# dual-ecal-RF-board.net
KiCad netlist of a schematic drawn in Altium Designer
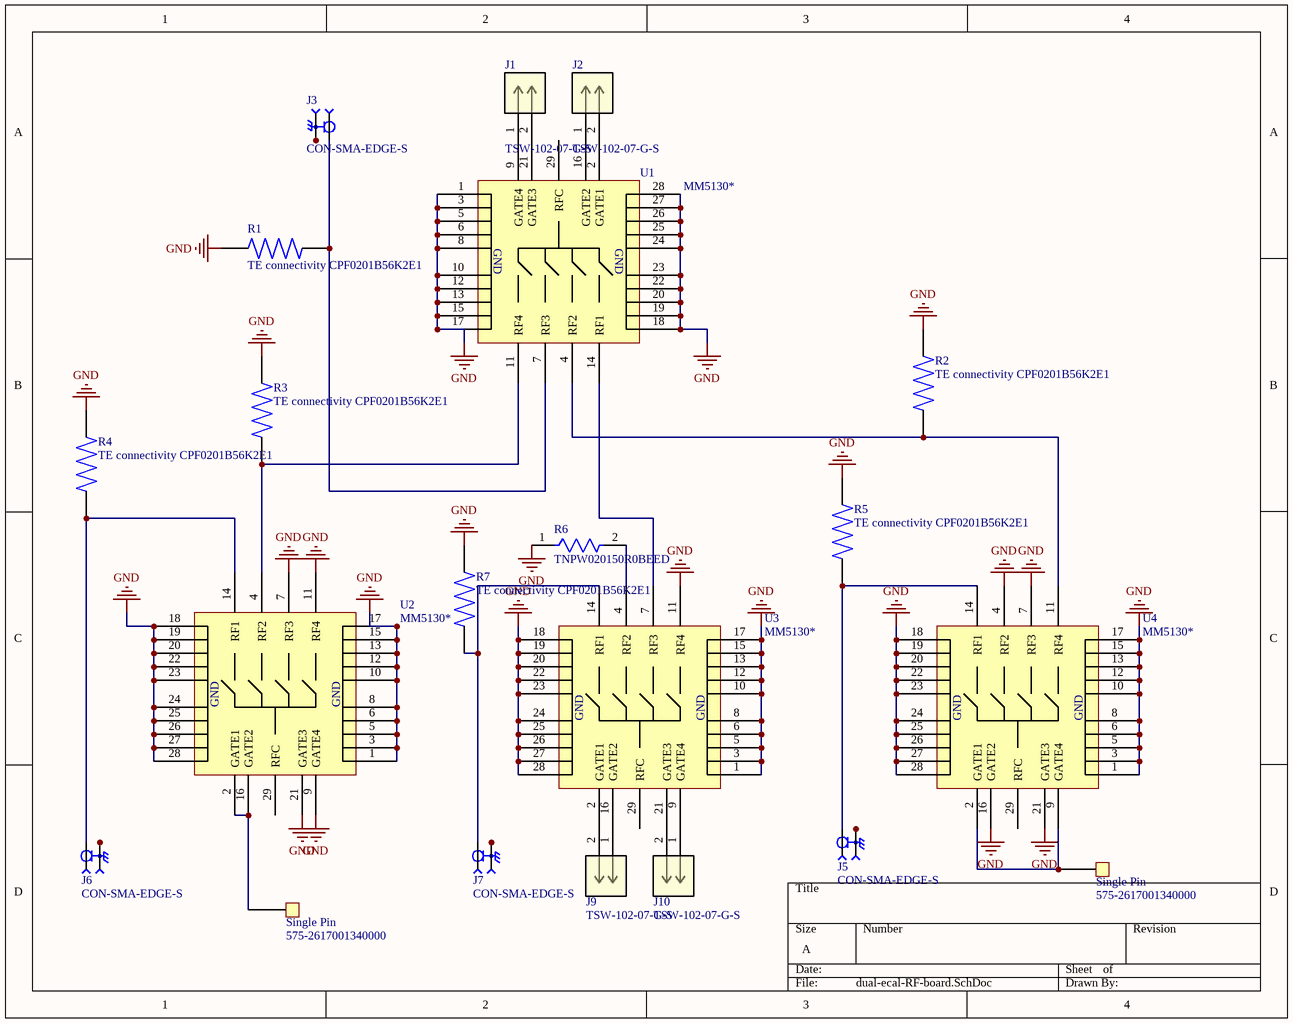
[diagram p0: dual-ecal-RF-board.SchDoc]

(export (version "E")
  (design (tool "Eeschema 10.0.6"))
  (components
    (comp (ref "J1")
      (value "TSW-102-07-G-S")
      (footprint "TSW-102-07-G-S-iceberg")
      (description "No Description Available")
      (fields (field (name "COPYRIGHT") "Copyright (C) 2024 Ultra Librarian. All rights reserved."))
      (libsource (lib "SchlibLafe") (part "TSW-102-07-G-S-iceberg"))
    )
    (comp (ref "J2")
      (value "TSW-102-07-G-S")
      (footprint "TSW-102-07-G-S-iceberg")
      (description "No Description Available")
      (fields (field (name "COPYRIGHT") "Copyright (C) 2024 Ultra Librarian. All rights reserved."))
      (libsource (lib "SchlibLafe") (part "TSW-102-07-G-S-iceberg"))
    )
    (comp (ref "J3")
      (value "CON-SMA-EDGE-S")
      (footprint "RFSOLUTIONS_CON-SMA-EDGE-S")
      (description "SMA Connector Jack, Female Socket - Board Edge, End Launch Solder")
      (fields (field (name "MF") "RF Solutions") (field (name "DIGI-KEY_PART_NUMBER") "CON-SMA-EDGE-S-ND"))
      (libsource (lib "SchlibLafe") (part "CON-SMA-EDGE-S"))
    )
    (comp (ref "J4")
      (value "Single Pin")
      (footprint "Single PC Pin")
      (fields (field (name "SUPPLIER PART NUMBER 1") "575-2617001340000"))
      (libsource (lib "SchlibLafe") (part "Single PC Pin"))
    )
    (comp (ref "J5")
      (value "CON-SMA-EDGE-S")
      (footprint "RFSOLUTIONS_CON-SMA-EDGE-S")
      (description "SMA Connector Jack, Female Socket - Board Edge, End Launch Solder")
      (fields (field (name "MF") "RF Solutions") (field (name "DIGI-KEY_PART_NUMBER") "CON-SMA-EDGE-S-ND"))
      (libsource (lib "SchlibLafe") (part "CON-SMA-EDGE-S"))
    )
    (comp (ref "J6")
      (value "CON-SMA-EDGE-S")
      (footprint "RFSOLUTIONS_CON-SMA-EDGE-S")
      (description "SMA Connector Jack, Female Socket - Board Edge, End Launch Solder")
      (fields (field (name "MF") "RF Solutions") (field (name "DIGI-KEY_PART_NUMBER") "CON-SMA-EDGE-S-ND"))
      (libsource (lib "SchlibLafe") (part "CON-SMA-EDGE-S"))
    )
    (comp (ref "J7")
      (value "CON-SMA-EDGE-S")
      (footprint "RFSOLUTIONS_CON-SMA-EDGE-S")
      (description "SMA Connector Jack, Female Socket - Board Edge, End Launch Solder")
      (fields (field (name "MF") "RF Solutions") (field (name "DIGI-KEY_PART_NUMBER") "CON-SMA-EDGE-S-ND"))
      (libsource (lib "SchlibLafe") (part "CON-SMA-EDGE-S"))
    )
    (comp (ref "J8")
      (value "Single Pin")
      (footprint "Single PC Pin")
      (fields (field (name "SUPPLIER PART NUMBER 1") "575-2617001340000"))
      (libsource (lib "SchlibLafe") (part "Single PC Pin"))
    )
    (comp (ref "J9")
      (value "TSW-102-07-G-S")
      (footprint "TSW-102-07-G-S-iceberg")
      (description "No Description Available")
      (fields (field (name "COPYRIGHT") "Copyright (C) 2024 Ultra Librarian. All rights reserved."))
      (libsource (lib "") (part "TSW-102-07-G-S-iceberg_1"))
    )
    (comp (ref "J10")
      (value "TSW-102-07-G-S")
      (footprint "TSW-102-07-G-S-iceberg")
      (description "No Description Available")
      (fields (field (name "COPYRIGHT") "Copyright (C) 2024 Ultra Librarian. All rights reserved."))
      (libsource (lib "") (part "TSW-102-07-G-S-iceberg_1"))
    )
    (comp (ref "R1")
      (value "TE connectivity CPF0201B56K2E1")
      (footprint "0201-resistor")
      (description "CPF 0201 56K2 0.1% 25PPM 1K RL")
      (fields (field (name "MP") "ERJ1GN0R00C") (field (name "MFGR PART NO.") "CPF0201B56K2E1"))
      (libsource (lib "SchlibLafe") (part "TE connectivity CPF0201B56K2E1"))
    )
    (comp (ref "R2")
      (value "TE connectivity CPF0201B56K2E1")
      (footprint "0201-resistor")
      (description "CPF 0201 56K2 0.1% 25PPM 1K RL")
      (fields (field (name "MP") "ERJ1GN0R00C") (field (name "MFGR PART NO.") "CPF0201B56K2E1"))
      (libsource (lib "SchlibLafe") (part "TE connectivity CPF0201B56K2E1"))
    )
    (comp (ref "R3")
      (value "TE connectivity CPF0201B56K2E1")
      (footprint "0201-resistor")
      (description "CPF 0201 56K2 0.1% 25PPM 1K RL")
      (fields (field (name "MP") "ERJ1GN0R00C") (field (name "MFGR PART NO.") "CPF0201B56K2E1"))
      (libsource (lib "SchlibLafe") (part "TE connectivity CPF0201B56K2E1"))
    )
    (comp (ref "R4")
      (value "TE connectivity CPF0201B56K2E1")
      (footprint "0201-resistor")
      (description "CPF 0201 56K2 0.1% 25PPM 1K RL")
      (fields (field (name "MP") "ERJ1GN0R00C") (field (name "MFGR PART NO.") "CPF0201B56K2E1"))
      (libsource (lib "SchlibLafe") (part "TE connectivity CPF0201B56K2E1"))
    )
    (comp (ref "R5")
      (value "TE connectivity CPF0201B56K2E1")
      (footprint "0201-resistor")
      (description "CPF 0201 56K2 0.1% 25PPM 1K RL")
      (fields (field (name "MP") "ERJ1GN0R00C") (field (name "MFGR PART NO.") "CPF0201B56K2E1"))
      (libsource (lib "SchlibLafe") (part "TE connectivity CPF0201B56K2E1"))
    )
    (comp (ref "R6")
      (value "TNPW020150R0BEED")
      (footprint "FP-ERJ1GN-IPC_C")
      (description "RES SMD 50 OHM 0.1% 1/20W 0201")
      (fields (field (name "TOLERANCE") "1%"))
      (libsource (lib "Altium Content Vault") (part "1029c3af85768c4190bb7ad29bc67b5"))
    )
    (comp (ref "R7")
      (value "TE connectivity CPF0201B56K2E1")
      (footprint "0201-resistor")
      (description "CPF 0201 56K2 0.1% 25PPM 1K RL")
      (fields (field (name "MP") "ERJ1GN0R00C") (field (name "MFGR PART NO.") "CPF0201B56K2E1"))
      (libsource (lib "SchlibLafe") (part "TE connectivity CPF0201B56K2E1"))
    )
    (comp (ref "U1")
      (value "MM5130*")
      (footprint "MM5130-NORM_PCB_NOFLOOD")
      (description "High power SP4T MEMs switch")
      (libsource (lib "") (part "IC-MM5130_1"))
    )
    (comp (ref "U2")
      (value "MM5130*")
      (footprint "MM5130-NORM_PCB_NOFLOOD")
      (description "High power SP4T MEMs switch")
      (libsource (lib "MM5130_SCHSYM") (part "IC-MM5130"))
    )
    (comp (ref "U3")
      (value "MM5130*")
      (footprint "MM5130-NORM_PCB_NOFLOOD")
      (description "High power SP4T MEMs switch")
      (libsource (lib "MM5130_SCHSYM") (part "IC-MM5130"))
    )
    (comp (ref "U4")
      (value "MM5130*")
      (footprint "MM5130-NORM_PCB_NOFLOOD")
      (description "High power SP4T MEMs switch")
      (libsource (lib "MM5130_SCHSYM") (part "IC-MM5130"))
    )
  )
  (nets
    (net (code "1") (name "GND") (class "Default")
      (node (ref "R1") (pin "1") (pinfunction "1_1") (pintype "passive"))
      (node (ref "R2") (pin "1") (pinfunction "1_1") (pintype "passive"))
      (node (ref "R3") (pin "1") (pinfunction "1_1") (pintype "passive"))
      (node (ref "R4") (pin "1") (pinfunction "1_1") (pintype "passive"))
      (node (ref "R5") (pin "1") (pinfunction "1_1") (pintype "passive"))
      (node (ref "R6") (pin "1") (pinfunction "1_1") (pintype "passive"))
      (node (ref "R7") (pin "1") (pinfunction "1_1") (pintype "passive"))
      (node (ref "U1") (pin "1") (pinfunction "GND_1") (pintype "passive"))
      (node (ref "U1") (pin "10") (pinfunction "GND_10") (pintype "passive"))
      (node (ref "U1") (pin "12") (pinfunction "GND_12") (pintype "passive"))
      (node (ref "U1") (pin "13") (pinfunction "GND_13") (pintype "passive"))
      (node (ref "U1") (pin "15") (pinfunction "GND_15") (pintype "passive"))
      (node (ref "U1") (pin "17") (pinfunction "GND_17") (pintype "passive"))
      (node (ref "U1") (pin "18") (pinfunction "GND_18") (pintype "passive"))
      (node (ref "U1") (pin "19") (pinfunction "GND_19") (pintype "passive"))
      (node (ref "U1") (pin "20") (pinfunction "GND_20") (pintype "passive"))
      (node (ref "U1") (pin "22") (pinfunction "GND_22") (pintype "passive"))
      (node (ref "U1") (pin "23") (pinfunction "GND_23") (pintype "passive"))
      (node (ref "U1") (pin "24") (pinfunction "GND_24") (pintype "passive"))
      (node (ref "U1") (pin "25") (pinfunction "GND_25") (pintype "passive"))
      (node (ref "U1") (pin "26") (pinfunction "GND_26") (pintype "passive"))
      (node (ref "U1") (pin "27") (pinfunction "GND_27") (pintype "passive"))
      (node (ref "U1") (pin "28") (pinfunction "GND_28") (pintype "passive"))
      (node (ref "U1") (pin "3") (pinfunction "GND_3") (pintype "passive"))
      (node (ref "U1") (pin "5") (pinfunction "GND_5") (pintype "passive"))
      (node (ref "U1") (pin "6") (pinfunction "GND_6") (pintype "passive"))
      (node (ref "U1") (pin "8") (pinfunction "GND_8") (pintype "passive"))
      (node (ref "U2") (pin "1") (pinfunction "GND_1") (pintype "passive"))
      (node (ref "U2") (pin "10") (pinfunction "GND_10") (pintype "passive"))
      (node (ref "U2") (pin "11") (pinfunction "RF4_11") (pintype "passive"))
      (node (ref "U2") (pin "12") (pinfunction "GND_12") (pintype "passive"))
      (node (ref "U2") (pin "13") (pinfunction "GND_13") (pintype "passive"))
      (node (ref "U2") (pin "15") (pinfunction "GND_15") (pintype "passive"))
      (node (ref "U2") (pin "17") (pinfunction "GND_17") (pintype "passive"))
      (node (ref "U2") (pin "18") (pinfunction "GND_18") (pintype "passive"))
      (node (ref "U2") (pin "19") (pinfunction "GND_19") (pintype "passive"))
      (node (ref "U2") (pin "20") (pinfunction "GND_20") (pintype "passive"))
      (node (ref "U2") (pin "21") (pinfunction "GATE3_21") (pintype "passive"))
      (node (ref "U2") (pin "22") (pinfunction "GND_22") (pintype "passive"))
      (node (ref "U2") (pin "23") (pinfunction "GND_23") (pintype "passive"))
      (node (ref "U2") (pin "24") (pinfunction "GND_24") (pintype "passive"))
      (node (ref "U2") (pin "25") (pinfunction "GND_25") (pintype "passive"))
      (node (ref "U2") (pin "26") (pinfunction "GND_26") (pintype "passive"))
      (node (ref "U2") (pin "27") (pinfunction "GND_27") (pintype "passive"))
      (node (ref "U2") (pin "28") (pinfunction "GND_28") (pintype "passive"))
      (node (ref "U2") (pin "3") (pinfunction "GND_3") (pintype "passive"))
      (node (ref "U2") (pin "5") (pinfunction "GND_5") (pintype "passive"))
      (node (ref "U2") (pin "6") (pinfunction "GND_6") (pintype "passive"))
      (node (ref "U2") (pin "7") (pinfunction "RF3_7") (pintype "passive"))
      (node (ref "U2") (pin "8") (pinfunction "GND_8") (pintype "passive"))
      (node (ref "U2") (pin "9") (pinfunction "GATE4_9") (pintype "passive"))
      (node (ref "U3") (pin "1") (pinfunction "GND_1") (pintype "passive"))
      (node (ref "U3") (pin "10") (pinfunction "GND_10") (pintype "passive"))
      (node (ref "U3") (pin "11") (pinfunction "RF4_11") (pintype "passive"))
      (node (ref "U3") (pin "12") (pinfunction "GND_12") (pintype "passive"))
      (node (ref "U3") (pin "13") (pinfunction "GND_13") (pintype "passive"))
      (node (ref "U3") (pin "15") (pinfunction "GND_15") (pintype "passive"))
      (node (ref "U3") (pin "17") (pinfunction "GND_17") (pintype "passive"))
      (node (ref "U3") (pin "18") (pinfunction "GND_18") (pintype "passive"))
      (node (ref "U3") (pin "19") (pinfunction "GND_19") (pintype "passive"))
      (node (ref "U3") (pin "20") (pinfunction "GND_20") (pintype "passive"))
      (node (ref "U3") (pin "22") (pinfunction "GND_22") (pintype "passive"))
      (node (ref "U3") (pin "23") (pinfunction "GND_23") (pintype "passive"))
      (node (ref "U3") (pin "24") (pinfunction "GND_24") (pintype "passive"))
      (node (ref "U3") (pin "25") (pinfunction "GND_25") (pintype "passive"))
      (node (ref "U3") (pin "26") (pinfunction "GND_26") (pintype "passive"))
      (node (ref "U3") (pin "27") (pinfunction "GND_27") (pintype "passive"))
      (node (ref "U3") (pin "28") (pinfunction "GND_28") (pintype "passive"))
      (node (ref "U3") (pin "3") (pinfunction "GND_3") (pintype "passive"))
      (node (ref "U3") (pin "5") (pinfunction "GND_5") (pintype "passive"))
      (node (ref "U3") (pin "6") (pinfunction "GND_6") (pintype "passive"))
      (node (ref "U3") (pin "8") (pinfunction "GND_8") (pintype "passive"))
      (node (ref "U4") (pin "1") (pinfunction "GND_1") (pintype "passive"))
      (node (ref "U4") (pin "10") (pinfunction "GND_10") (pintype "passive"))
      (node (ref "U4") (pin "12") (pinfunction "GND_12") (pintype "passive"))
      (node (ref "U4") (pin "13") (pinfunction "GND_13") (pintype "passive"))
      (node (ref "U4") (pin "15") (pinfunction "GND_15") (pintype "passive"))
      (node (ref "U4") (pin "16") (pinfunction "GATE2_16") (pintype "passive"))
      (node (ref "U4") (pin "17") (pinfunction "GND_17") (pintype "passive"))
      (node (ref "U4") (pin "18") (pinfunction "GND_18") (pintype "passive"))
      (node (ref "U4") (pin "19") (pinfunction "GND_19") (pintype "passive"))
      (node (ref "U4") (pin "20") (pinfunction "GND_20") (pintype "passive"))
      (node (ref "U4") (pin "21") (pinfunction "GATE3_21") (pintype "passive"))
      (node (ref "U4") (pin "22") (pinfunction "GND_22") (pintype "passive"))
      (node (ref "U4") (pin "23") (pinfunction "GND_23") (pintype "passive"))
      (node (ref "U4") (pin "24") (pinfunction "GND_24") (pintype "passive"))
      (node (ref "U4") (pin "25") (pinfunction "GND_25") (pintype "passive"))
      (node (ref "U4") (pin "26") (pinfunction "GND_26") (pintype "passive"))
      (node (ref "U4") (pin "27") (pinfunction "GND_27") (pintype "passive"))
      (node (ref "U4") (pin "28") (pinfunction "GND_28") (pintype "passive"))
      (node (ref "U4") (pin "3") (pinfunction "GND_3") (pintype "passive"))
      (node (ref "U4") (pin "4") (pinfunction "RF2_4") (pintype "passive"))
      (node (ref "U4") (pin "5") (pinfunction "GND_5") (pintype "passive"))
      (node (ref "U4") (pin "6") (pinfunction "GND_6") (pintype "passive"))
      (node (ref "U4") (pin "7") (pinfunction "RF3_7") (pintype "passive"))
      (node (ref "U4") (pin "8") (pinfunction "GND_8") (pintype "passive"))
    )
    (net (code "2") (name "Net-(J3-2-PadG1)") (class "Default")
      (node (ref "J3") (pin "G1") (pinfunction "2_G1") (pintype "passive"))
      (node (ref "J3") (pin "G2") (pinfunction "2_G2") (pintype "passive"))
      (node (ref "J3") (pin "G3") (pinfunction "2_G3") (pintype "passive"))
      (node (ref "J3") (pin "G4") (pinfunction "2_G4") (pintype "passive"))
    )
    (net (code "3") (name "Net-(J5-2-PadG1)") (class "Default")
      (node (ref "J5") (pin "G1") (pinfunction "2_G1") (pintype "passive"))
      (node (ref "J5") (pin "G2") (pinfunction "2_G2") (pintype "passive"))
      (node (ref "J5") (pin "G3") (pinfunction "2_G3") (pintype "passive"))
      (node (ref "J5") (pin "G4") (pinfunction "2_G4") (pintype "passive"))
    )
    (net (code "4") (name "Net-(J6-2-PadG1)") (class "Default")
      (node (ref "J6") (pin "G1") (pinfunction "2_G1") (pintype "passive"))
      (node (ref "J6") (pin "G2") (pinfunction "2_G2") (pintype "passive"))
      (node (ref "J6") (pin "G3") (pinfunction "2_G3") (pintype "passive"))
      (node (ref "J6") (pin "G4") (pinfunction "2_G4") (pintype "passive"))
    )
    (net (code "5") (name "Net-(J7-2-PadG1)") (class "Default")
      (node (ref "J7") (pin "G1") (pinfunction "2_G1") (pintype "passive"))
      (node (ref "J7") (pin "G2") (pinfunction "2_G2") (pintype "passive"))
      (node (ref "J7") (pin "G3") (pinfunction "2_G3") (pintype "passive"))
      (node (ref "J7") (pin "G4") (pinfunction "2_G4") (pintype "passive"))
    )
    (net (code "6") (name "Net-(U1-GATE1)") (class "Default")
      (node (ref "J2") (pin "2") (pinfunction "2_2") (pintype "passive"))
      (node (ref "U1") (pin "2") (pinfunction "GATE1_2") (pintype "passive"))
    )
    (net (code "7") (name "Net-(U1-GATE2)") (class "Default")
      (node (ref "J2") (pin "1") (pinfunction "1_1") (pintype "passive"))
      (node (ref "U1") (pin "16") (pinfunction "GATE2_16") (pintype "passive"))
    )
    (net (code "8") (name "Net-(U1-GATE3)") (class "Default")
      (node (ref "J1") (pin "2") (pinfunction "2_2") (pintype "passive"))
      (node (ref "U1") (pin "21") (pinfunction "GATE3_21") (pintype "passive"))
    )
    (net (code "9") (name "Net-(U1-GATE4)") (class "Default")
      (node (ref "J1") (pin "1") (pinfunction "1_1") (pintype "passive"))
      (node (ref "U1") (pin "9") (pinfunction "GATE4_9") (pintype "passive"))
    )
    (net (code "10") (name "Net-(U1-RF1)") (class "Default")
      (node (ref "U1") (pin "14") (pinfunction "RF1_14") (pintype "passive"))
      (node (ref "U3") (pin "7") (pinfunction "RF3_7") (pintype "passive"))
    )
    (net (code "11") (name "Net-(U1-RF2)") (class "Default")
      (node (ref "R2") (pin "2") (pinfunction "2_2") (pintype "passive"))
      (node (ref "U1") (pin "4") (pinfunction "RF2_4") (pintype "passive"))
      (node (ref "U4") (pin "11") (pinfunction "RF4_11") (pintype "passive"))
    )
    (net (code "12") (name "Net-(U1-RF3)") (class "Default")
      (node (ref "J3") (pin "1") (pinfunction "1_1") (pintype "passive"))
      (node (ref "R1") (pin "2") (pinfunction "2_2") (pintype "passive"))
      (node (ref "U1") (pin "7") (pinfunction "RF3_7") (pintype "passive"))
    )
    (net (code "13") (name "Net-(U1-RF4)") (class "Default")
      (node (ref "R3") (pin "2") (pinfunction "2_2") (pintype "passive"))
      (node (ref "U1") (pin "11") (pinfunction "RF4_11") (pintype "passive"))
      (node (ref "U2") (pin "4") (pinfunction "RF2_4") (pintype "passive"))
    )
    (net (code "14") (name "Net-(U2-GATE1)") (class "Default")
      (node (ref "J8") (pin "1") (pinfunction "1_1") (pintype "passive"))
      (node (ref "U2") (pin "16") (pinfunction "GATE2_16") (pintype "passive"))
      (node (ref "U2") (pin "2") (pinfunction "GATE1_2") (pintype "passive"))
    )
    (net (code "15") (name "Net-(U2-RF1)") (class "Default")
      (node (ref "J6") (pin "1") (pinfunction "1_1") (pintype "passive"))
      (node (ref "R4") (pin "2") (pinfunction "2_2") (pintype "passive"))
      (node (ref "U2") (pin "14") (pinfunction "RF1_14") (pintype "passive"))
    )
    (net (code "16") (name "Net-(U3-GATE1)") (class "Default")
      (node (ref "J9") (pin "2") (pinfunction "2_2") (pintype "passive"))
      (node (ref "U3") (pin "2") (pinfunction "GATE1_2") (pintype "passive"))
    )
    (net (code "17") (name "Net-(U3-GATE2)") (class "Default")
      (node (ref "J9") (pin "1") (pinfunction "1_1") (pintype "passive"))
      (node (ref "U3") (pin "16") (pinfunction "GATE2_16") (pintype "passive"))
    )
    (net (code "18") (name "Net-(U3-GATE3)") (class "Default")
      (node (ref "J10") (pin "2") (pinfunction "2_2") (pintype "passive"))
      (node (ref "U3") (pin "21") (pinfunction "GATE3_21") (pintype "passive"))
    )
    (net (code "19") (name "Net-(U3-GATE4)") (class "Default")
      (node (ref "J10") (pin "1") (pinfunction "1_1") (pintype "passive"))
      (node (ref "U3") (pin "9") (pinfunction "GATE4_9") (pintype "passive"))
    )
    (net (code "20") (name "Net-(U3-RF1)") (class "Default")
      (node (ref "J7") (pin "1") (pinfunction "1_1") (pintype "passive"))
      (node (ref "R7") (pin "2") (pinfunction "2_2") (pintype "passive"))
      (node (ref "U3") (pin "14") (pinfunction "RF1_14") (pintype "passive"))
    )
    (net (code "21") (name "Net-(U3-RF2)") (class "Default")
      (node (ref "R6") (pin "2") (pinfunction "2_2") (pintype "passive"))
      (node (ref "U3") (pin "4") (pinfunction "RF2_4") (pintype "passive"))
    )
    (net (code "22") (name "Net-(U4-GATE1)") (class "Default")
      (node (ref "J4") (pin "1") (pinfunction "1_1") (pintype "passive"))
      (node (ref "U4") (pin "2") (pinfunction "GATE1_2") (pintype "passive"))
      (node (ref "U4") (pin "9") (pinfunction "GATE4_9") (pintype "passive"))
    )
    (net (code "23") (name "Net-(U4-RF1)") (class "Default")
      (node (ref "J5") (pin "1") (pinfunction "1_1") (pintype "passive"))
      (node (ref "R5") (pin "2") (pinfunction "2_2") (pintype "passive"))
      (node (ref "U4") (pin "14") (pinfunction "RF1_14") (pintype "passive"))
    )
    (net (code "24") (name "unconnected-(U1-RFC-Pad29)") (class "Default")
      (node (ref "U1") (pin "29") (pinfunction "RFC_29") (pintype "passive"))
    )
    (net (code "25") (name "unconnected-(U2-RFC-Pad29)") (class "Default")
      (node (ref "U2") (pin "29") (pinfunction "RFC_29") (pintype "passive"))
    )
    (net (code "26") (name "unconnected-(U3-RFC-Pad29)") (class "Default")
      (node (ref "U3") (pin "29") (pinfunction "RFC_29") (pintype "passive"))
    )
    (net (code "27") (name "unconnected-(U4-RFC-Pad29)") (class "Default")
      (node (ref "U4") (pin "29") (pinfunction "RFC_29") (pintype "passive"))
    )
  )
)
